# iF11M.net
KiCad netlist of a schematic drawn in Altium Designer
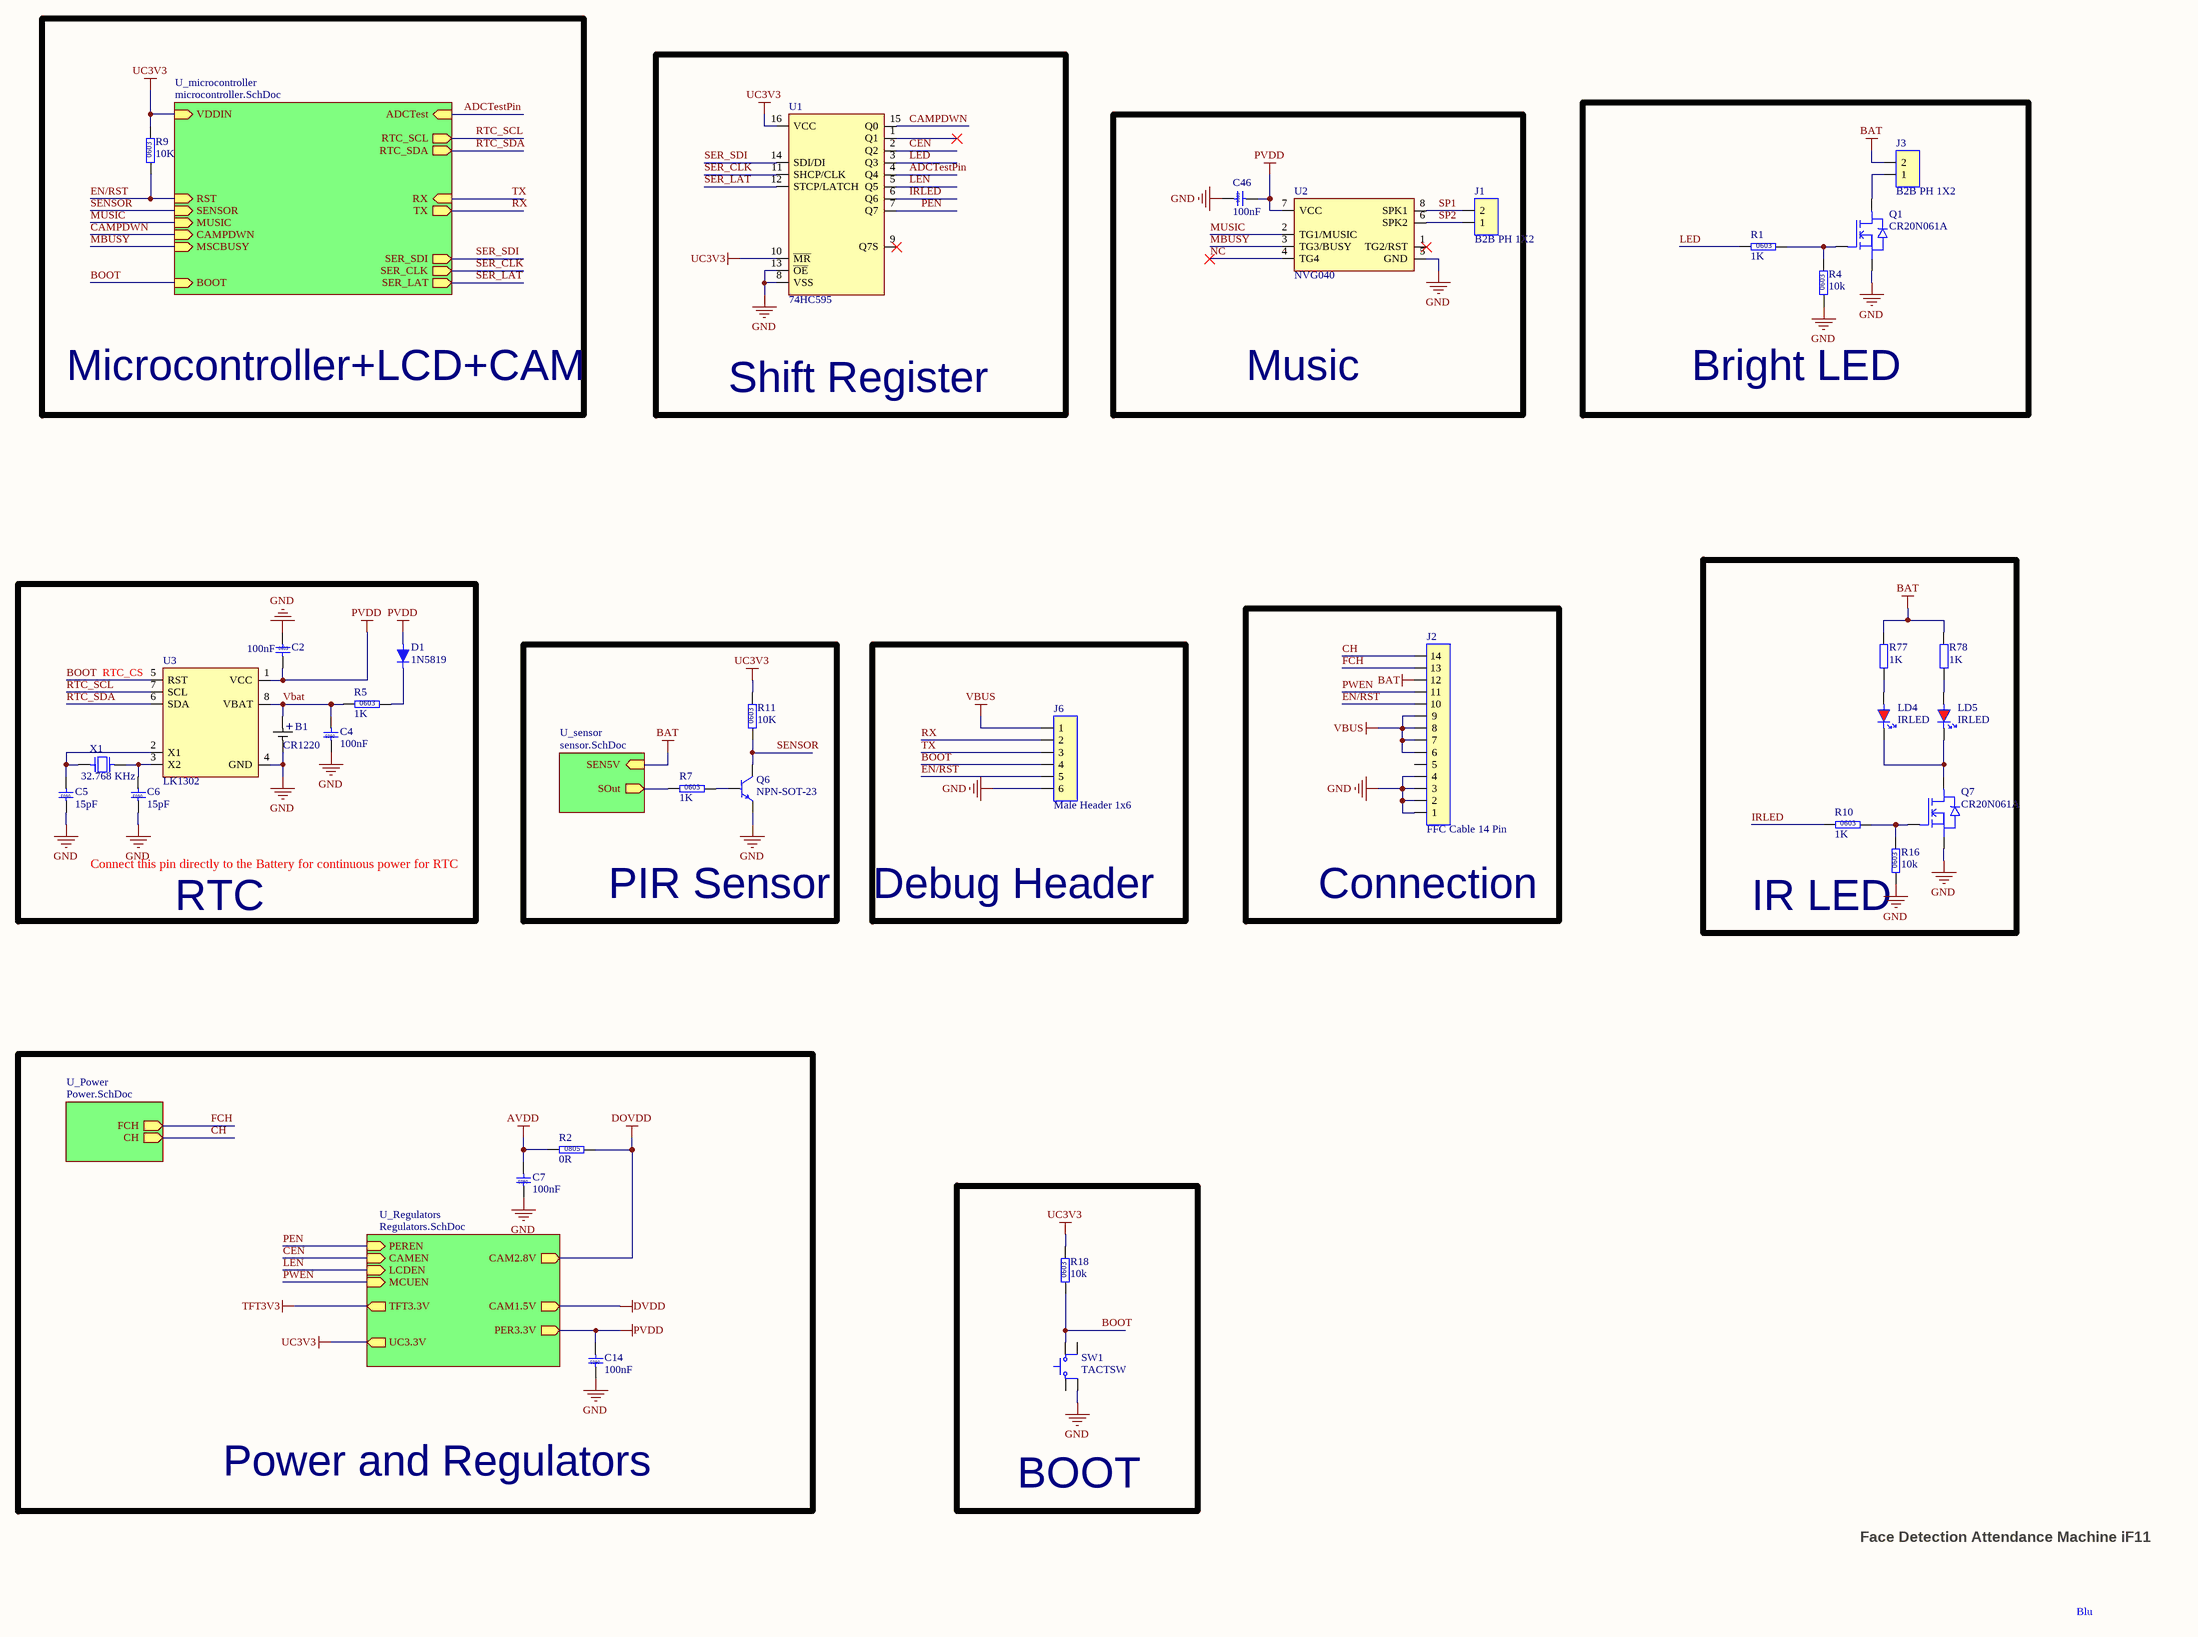
[diagram p0: iF11M.SchDoc]

(export (version "E")
  (design (tool "Eeschema 10.0.6"))
  (components
    (comp (ref "B1") (value "CR1220") (footprint "CR1220") (libsource (lib "Others") (part "CR1220")))
    (comp (ref "C2")
      (value "100nF")
      (footprint "C0603")
      (description "10% 50V")
      (fields (field (name "PART NO") "W-T-CA-X703N100K50VNT") (field (name "MANUFACTURER") "FENGHUA"))
      (libsource (lib "Rescap") (part "C 0603 100nF 50V"))
    )
    (comp (ref "C4")
      (value "100nF")
      (footprint "C0603")
      (description "10% 50V")
      (fields (field (name "PART NO") "W-T-CA-X703N100K50VNT") (field (name "MANUFACTURER") "FENGHUA"))
      (libsource (lib "Rescap") (part "C 0603 100nF 50V"))
    )
    (comp (ref "C5")
      (value "15pF")
      (footprint "C0603")
      (description "5% 25V")
      (fields (field (name "PART NO") "W-T-CA-CG03P010J25VNT"))
      (libsource (lib "Rescap") (part "C 0603 10pF 25V"))
    )
    (comp (ref "C6")
      (value "15pF")
      (footprint "C0603")
      (description "5% 25V")
      (fields (field (name "PART NO") "W-T-CA-CG03P010J25VNT"))
      (libsource (lib "Rescap") (part "C 0603 10pF 25V"))
    )
    (comp (ref "C7")
      (value "100nF")
      (footprint "C0603")
      (description "10% 50V")
      (fields (field (name "PART NO") "W-T-CA-X703N100K50VNT") (field (name "MANUFACTURER") "FENGHUA"))
      (libsource (lib "Rescap") (part "C 0603 100nF 50V"))
    )
    (comp (ref "C14")
      (value "100nF")
      (footprint "C0603")
      (description "10% 50V")
      (fields (field (name "PART NO") "W-T-CA-X703N100K50VNT") (field (name "MANUFACTURER") "FENGHUA"))
      (libsource (lib "Rescap") (part "C 0603 100nF 50V"))
    )
    (comp (ref "C46")
      (value "100nF")
      (footprint "C0603")
      (description "10% 50V")
      (fields (field (name "PART NO") "W-T-CA-X703N100K50VNT") (field (name "MANUFACTURER") "FENGHUA"))
      (libsource (lib "Rescap") (part "C 0603 100nF 50V"))
    )
    (comp (ref "D1") (value "1N5819") (footprint "SOD-323") (libsource (lib "Rectifier") (part "IN4148")))
    (comp (ref "J1")
      (value "B2B PH 1X2")
      (footprint "B2B-PH-2mm")
      (description "2 Pin B2B Connector")
      (libsource (lib "Connector") (part "B2B-PH-2MM"))
    )
    (comp (ref "J2")
      (value "FFC Cable 14 Pin")
      (footprint "FPC14P-1.2mm-THT")
      (libsource (lib "Connector") (part "FFC14P"))
    )
    (comp (ref "J3")
      (value "B2B PH 1X2")
      (footprint "B2B-PH-2mm")
      (description "2 Pin B2B Connector")
      (libsource (lib "Connector") (part "B2B-PH-2MM"))
    )
    (comp (ref "J6")
      (value "Male Header 1x6")
      (footprint "MHEADER-1x6")
      (description "6 Pin Male Header")
      (libsource (lib "Connector") (part "MHeader-1x6"))
    )
    (comp (ref "LD4")
      (value "IRLED")
      (footprint "LED 5mm RED Bent")
      (libsource (lib "Optoelectronics") (part "IRLED"))
    )
    (comp (ref "LD5")
      (value "IRLED")
      (footprint "LED 5mm RED Bent")
      (libsource (lib "Optoelectronics") (part "IRLED"))
    )
    (comp (ref "Q1")
      (value "CR20N061A")
      (footprint "NMOS-SOT23")
      (description "MOSFET-N-Channel")
      (libsource (lib "Transistor") (part "MOSFET-N-Channel"))
    )
    (comp (ref "Q6")
      (value "NPN-SOT-23")
      (footprint "SOT23")
      (libsource (lib "Transistor") (part "NPN-SOT-23"))
    )
    (comp (ref "Q7")
      (value "CR20N061A")
      (footprint "NMOS-SOT23")
      (description "MOSFET-N-Channel")
      (libsource (lib "Transistor") (part "MOSFET-N-Channel"))
    )
    (comp (ref "R1")
      (value "1K")
      (footprint "R0603-LD")
      (description "5%")
      (fields (field (name "PART NO") "W-T-RE-RS03K103JT") (field (name "MANUFACTURER") "热敏D541V11增加1颗用量"))
      (libsource (lib "Rescap") (part "R 0603 10k"))
    )
    (comp (ref "R2")
      (value "0R")
      (footprint "R0805-LD")
      (description "1%")
      (fields (field (name "PART NO") "W-T-RE-RS05K0R0JT"))
      (libsource (lib "Rescap") (part "R 0805 0R"))
    )
    (comp (ref "R4")
      (value "10k")
      (footprint "R0603-LD")
      (description "5%")
      (fields (field (name "PART NO") "W-T-RE-RS03K103JT") (field (name "MANUFACTURER") "热敏D541V11增加1颗用量"))
      (libsource (lib "Rescap") (part "R 0603 10k"))
    )
    (comp (ref "R5")
      (value "1K")
      (footprint "R0603-LD")
      (description "5%")
      (fields (field (name "PART NO") "W-T-RE-RS03K103JT") (field (name "MANUFACTURER") "热敏D541V11增加1颗用量"))
      (libsource (lib "Rescap") (part "R 0603 10k"))
    )
    (comp (ref "R7")
      (value "1K")
      (footprint "R0603-LD")
      (description "5%")
      (fields (field (name "PART NO") "W-T-RE-RS03K103JT") (field (name "MANUFACTURER") "热敏D541V11增加1颗用量"))
      (libsource (lib "Rescap") (part "R 0603 10k"))
    )
    (comp (ref "R9")
      (value "10K")
      (footprint "R0603-LD")
      (description "5%")
      (fields (field (name "PART NO") "W-T-RE-RS03K103JT") (field (name "MANUFACTURER") "热敏D541V11增加1颗用量"))
      (libsource (lib "Rescap") (part "R 0603 10K"))
    )
    (comp (ref "R10")
      (value "1K")
      (footprint "R0603-LD")
      (description "5%")
      (fields (field (name "PART NO") "W-T-RE-RS03K103JT") (field (name "MANUFACTURER") "热敏D541V11增加1颗用量"))
      (libsource (lib "Rescap") (part "R 0603 10k"))
    )
    (comp (ref "R11")
      (value "10K")
      (footprint "R0603-LD")
      (description "5%")
      (fields (field (name "PART NO") "W-T-RE-RS03K103JT") (field (name "MANUFACTURER") "热敏D541V11增加1颗用量"))
      (libsource (lib "Rescap") (part "R 0603 10K"))
    )
    (comp (ref "R16")
      (value "10k")
      (footprint "R0603-LD")
      (description "5%")
      (fields (field (name "PART NO") "W-T-RE-RS03K103JT") (field (name "MANUFACTURER") "热敏D541V11增加1颗用量"))
      (libsource (lib "Rescap") (part "R 0603 10k"))
    )
    (comp (ref "R18")
      (value "10k")
      (footprint "R0603-LD")
      (description "5%")
      (fields (field (name "PART NO") "W-T-RE-RS03K103JT") (field (name "MANUFACTURER") "热敏D541V11增加1颗用量"))
      (libsource (lib "Rescap") (part "R 0603 10k"))
    )
    (comp (ref "R77") (value "1K") (footprint "R0805") (libsource (lib "Resistor") (part "Resistor")))
    (comp (ref "R78") (value "1K") (footprint "R0805") (libsource (lib "Resistor") (part "Resistor")))
    (comp (ref "SW1")
      (value "TACTSW")
      (footprint "SMDtactswitch-5x5")
      (description "2 pin tactile switch round")
      (libsource (lib "Switch") (part "Tactile-smd_1"))
    )
    (comp (ref "U1")
      (value "74HC595")
      (footprint "SOIC16")
      (description "8bit Serial/Parallel Shift Register")
      (libsource (lib "mylib2") (part "74595"))
    )
    (comp (ref "U2") (value "NVG040") (footprint "SOP-8") (libsource (lib "mylib2") (part "NVG040")))
    (comp (ref "U3")
      (value "LK1302")
      (footprint "SOP-8")
      (description "Trickle-Charge Timekeeping Chip")
      (libsource (lib "mylib2") (part "LK1302"))
    )
    (comp (ref "X1")
      (value "32.768 KHz")
      (footprint "RTC Crystal")
      (description "RTC Crystal")
      (libsource (lib "Others") (part "Crystal_RTC"))
    )
  )
  (nets
    (net (code "1") (name "/ADCTestPin") (class "Default")
      (node (ref "U1") (pin "4") (pinfunction "Q4_4") (pintype "passive"))
    )
    (net (code "2") (name "/BOOT") (class "Default")
      (node (ref "J6") (pin "4") (pinfunction "4_4") (pintype "passive"))
      (node (ref "R18") (pin "1") (pinfunction "1_1") (pintype "passive"))
      (node (ref "SW1") (pin "4") (pinfunction "4_4") (pintype "passive"))
      (node (ref "U3") (pin "5") (pinfunction "RST_5") (pintype "passive"))
    )
    (net (code "3") (name "/CAMPDWN") (class "Default")
      (node (ref "U1") (pin "15") (pinfunction "Q0_15") (pintype "passive"))
    )
    (net (code "4") (name "/CEN") (class "Default")
      (node (ref "U1") (pin "2") (pinfunction "Q2_2") (pintype "passive"))
    )
    (net (code "5") (name "/CH") (class "Default")
      (node (ref "J2") (pin "14") (pinfunction "14_14") (pintype "passive"))
    )
    (net (code "6") (name "/EN{slash}RST") (class "Default")
      (node (ref "J2") (pin "10") (pinfunction "10_10") (pintype "passive"))
      (node (ref "J6") (pin "5") (pinfunction "5_5") (pintype "passive"))
      (node (ref "R9") (pin "1") (pinfunction "1_1") (pintype "passive"))
    )
    (net (code "7") (name "/FCH") (class "Default")
      (node (ref "J2") (pin "13") (pinfunction "13_13") (pintype "passive"))
    )
    (net (code "8") (name "/IRLED") (class "Default")
      (node (ref "R10") (pin "1") (pinfunction "1_1") (pintype "passive"))
      (node (ref "U1") (pin "6") (pinfunction "Q6_6") (pintype "passive"))
    )
    (net (code "9") (name "/LED") (class "Default")
      (node (ref "R1") (pin "1") (pinfunction "1_1") (pintype "passive"))
      (node (ref "U1") (pin "3") (pinfunction "Q3_3") (pintype "passive"))
    )
    (net (code "10") (name "/LEN") (class "Default")
      (node (ref "U1") (pin "5") (pinfunction "Q5_5") (pintype "passive"))
    )
    (net (code "11") (name "/MBUSY") (class "Default")
      (node (ref "U2") (pin "3") (pinfunction "TG3/BUSY_3") (pintype "passive"))
    )
    (net (code "12") (name "/MUSIC") (class "Default")
      (node (ref "U2") (pin "2") (pinfunction "TG1/MUSIC_2") (pintype "passive"))
    )
    (net (code "13") (name "/NC") (class "Default")
      (node (ref "U2") (pin "4") (pinfunction "TG4_4") (pintype "passive+no_connect"))
    )
    (net (code "14") (name "/PEN") (class "Default")
      (node (ref "U1") (pin "7") (pinfunction "Q7_7") (pintype "passive"))
    )
    (net (code "15") (name "/PWEN") (class "Default")
      (node (ref "J2") (pin "11") (pinfunction "11_11") (pintype "passive"))
    )
    (net (code "16") (name "/RTC_SCL") (class "Default")
      (node (ref "U3") (pin "7") (pinfunction "SCL_7") (pintype "passive"))
    )
    (net (code "17") (name "/RTC_SDA") (class "Default")
      (node (ref "U3") (pin "6") (pinfunction "SDA_6") (pintype "passive"))
    )
    (net (code "18") (name "/RX") (class "Default")
      (node (ref "J6") (pin "2") (pinfunction "2_2") (pintype "passive"))
    )
    (net (code "19") (name "/SENSOR") (class "Default")
      (node (ref "Q6") (pin "3") (pinfunction "C_3") (pintype "passive"))
      (node (ref "R11") (pin "1") (pinfunction "1_1") (pintype "passive"))
    )
    (net (code "20") (name "/SER_CLK") (class "Default")
      (node (ref "U1") (pin "11") (pinfunction "SHCP/CLK_11") (pintype "passive"))
    )
    (net (code "21") (name "/SER_LAT") (class "Default")
      (node (ref "U1") (pin "12") (pinfunction "STCP/LATCH_12") (pintype "passive"))
    )
    (net (code "22") (name "/SER_SDI") (class "Default")
      (node (ref "U1") (pin "14") (pinfunction "SDI/DI_14") (pintype "passive"))
    )
    (net (code "23") (name "/SOut") (class "Default")
      (node (ref "R7") (pin "1") (pinfunction "1_1") (pintype "passive"))
    )
    (net (code "24") (name "/SP1") (class "Default")
      (node (ref "J1") (pin "2") (pinfunction "2_2") (pintype "passive"))
      (node (ref "U2") (pin "8") (pinfunction "SPK1_8") (pintype "passive"))
    )
    (net (code "25") (name "/SP2") (class "Default")
      (node (ref "J1") (pin "1") (pinfunction "1_1") (pintype "passive"))
      (node (ref "U2") (pin "6") (pinfunction "SPK2_6") (pintype "passive"))
    )
    (net (code "26") (name "/TX") (class "Default")
      (node (ref "J6") (pin "3") (pinfunction "3_3") (pintype "passive"))
    )
    (net (code "27") (name "/Vbat") (class "Default")
      (node (ref "B1") (pin "2") (pinfunction "2_2") (pintype "passive"))
      (node (ref "C4") (pin "2") (pinfunction "2_2") (pintype "passive"))
      (node (ref "R5") (pin "1") (pinfunction "1_1") (pintype "passive"))
      (node (ref "U3") (pin "8") (pinfunction "VBAT_8") (pintype "passive"))
    )
    (net (code "28") (name "AVDD") (class "Default")
      (node (ref "C7") (pin "2") (pinfunction "2_2") (pintype "passive"))
      (node (ref "R2") (pin "1") (pinfunction "1_1") (pintype "passive"))
    )
    (net (code "29") (name "BAT") (class "Default")
      (node (ref "J2") (pin "12") (pinfunction "12_12") (pintype "passive"))
      (node (ref "J3") (pin "2") (pinfunction "2_2") (pintype "passive"))
      (node (ref "R77") (pin "2") (pinfunction "2_2") (pintype "passive"))
      (node (ref "R78") (pin "2") (pinfunction "2_2") (pintype "passive"))
    )
    (net (code "30") (name "DOVDD") (class "Default")
      (node (ref "R2") (pin "2") (pinfunction "2_2") (pintype "passive"))
    )
    (net (code "32") (name "GND") (class "Default")
      (node (ref "B1") (pin "1") (pinfunction "1_1") (pintype "passive"))
      (node (ref "C14") (pin "1") (pinfunction "1_1") (pintype "passive"))
      (node (ref "C2") (pin "1") (pinfunction "1_1") (pintype "passive"))
      (node (ref "C4") (pin "1") (pinfunction "1_1") (pintype "passive"))
      (node (ref "C46") (pin "1") (pinfunction "1_1") (pintype "passive"))
      (node (ref "C5") (pin "1") (pinfunction "1_1") (pintype "passive"))
      (node (ref "C6") (pin "1") (pinfunction "1_1") (pintype "passive"))
      (node (ref "C7") (pin "1") (pinfunction "1_1") (pintype "passive"))
      (node (ref "J2") (pin "1") (pinfunction "1_1") (pintype "passive"))
      (node (ref "J2") (pin "2") (pinfunction "2_2") (pintype "passive"))
      (node (ref "J2") (pin "3") (pinfunction "3_3") (pintype "passive"))
      (node (ref "J2") (pin "4") (pinfunction "4_4") (pintype "passive"))
      (node (ref "J6") (pin "6") (pinfunction "6_6") (pintype "passive"))
      (node (ref "Q1") (pin "3") (pinfunction "S_3") (pintype "passive"))
      (node (ref "Q6") (pin "2") (pinfunction "E_2") (pintype "passive"))
      (node (ref "Q7") (pin "3") (pinfunction "S_3") (pintype "passive"))
      (node (ref "R16") (pin "1") (pinfunction "1_1") (pintype "passive"))
      (node (ref "R4") (pin "1") (pinfunction "1_1") (pintype "passive"))
      (node (ref "SW1") (pin "2") (pinfunction "2_2") (pintype "passive"))
      (node (ref "U1") (pin "13") (pinfunction "~{OE}_13") (pintype "passive"))
      (node (ref "U1") (pin "8") (pinfunction "VSS_8") (pintype "passive"))
      (node (ref "U2") (pin "5") (pinfunction "GND_5") (pintype "passive"))
      (node (ref "U3") (pin "4") (pinfunction "GND_4") (pintype "passive"))
    )
    (net (code "33") (name "Net-(D1-K)") (class "Default")
      (node (ref "D1") (pin "2") (pinfunction "K_2") (pintype "passive"))
      (node (ref "R5") (pin "2") (pinfunction "2_2") (pintype "passive"))
    )
    (net (code "34") (name "Net-(LD4-A)") (class "Default")
      (node (ref "LD4") (pin "1") (pinfunction "A_1") (pintype "passive"))
      (node (ref "R77") (pin "1") (pinfunction "1_1") (pintype "passive"))
    )
    (net (code "35") (name "Net-(LD4-K)") (class "Default")
      (node (ref "LD4") (pin "2") (pinfunction "K_2") (pintype "passive"))
      (node (ref "LD5") (pin "2") (pinfunction "K_2") (pintype "passive"))
      (node (ref "Q7") (pin "2") (pinfunction "D_2") (pintype "passive"))
    )
    (net (code "36") (name "Net-(LD5-A)") (class "Default")
      (node (ref "LD5") (pin "1") (pinfunction "A_1") (pintype "passive"))
      (node (ref "R78") (pin "1") (pinfunction "1_1") (pintype "passive"))
    )
    (net (code "37") (name "Net-(Q1-D)") (class "Default")
      (node (ref "J3") (pin "1") (pinfunction "1_1") (pintype "passive"))
      (node (ref "Q1") (pin "2") (pinfunction "D_2") (pintype "passive"))
    )
    (net (code "38") (name "Net-(Q1-G)") (class "Default")
      (node (ref "Q1") (pin "1") (pinfunction "G_1") (pintype "passive"))
      (node (ref "R1") (pin "2") (pinfunction "2_2") (pintype "passive"))
      (node (ref "R4") (pin "2") (pinfunction "2_2") (pintype "passive"))
    )
    (net (code "39") (name "Net-(Q6-B)") (class "Default")
      (node (ref "Q6") (pin "1") (pinfunction "B_1") (pintype "passive"))
      (node (ref "R7") (pin "2") (pinfunction "2_2") (pintype "passive"))
    )
    (net (code "40") (name "Net-(Q7-G)") (class "Default")
      (node (ref "Q7") (pin "1") (pinfunction "G_1") (pintype "passive"))
      (node (ref "R10") (pin "2") (pinfunction "2_2") (pintype "passive"))
      (node (ref "R16") (pin "2") (pinfunction "2_2") (pintype "passive"))
    )
    (net (code "41") (name "Net-(U3-X1)") (class "Default")
      (node (ref "C5") (pin "2") (pinfunction "2_2") (pintype "passive"))
      (node (ref "U3") (pin "2") (pinfunction "X1_2") (pintype "passive"))
      (node (ref "X1") (pin "2") (pinfunction "2_2") (pintype "passive"))
    )
    (net (code "42") (name "Net-(U3-X2)") (class "Default")
      (node (ref "C6") (pin "2") (pinfunction "2_2") (pintype "passive"))
      (node (ref "U3") (pin "3") (pinfunction "X2_3") (pintype "passive"))
      (node (ref "X1") (pin "1") (pinfunction "1_1") (pintype "passive"))
    )
    (net (code "43") (name "PVDD") (class "Default")
      (node (ref "C14") (pin "2") (pinfunction "2_2") (pintype "passive"))
      (node (ref "C2") (pin "2") (pinfunction "2_2") (pintype "passive"))
      (node (ref "C46") (pin "2") (pinfunction "2_2") (pintype "passive"))
      (node (ref "D1") (pin "1") (pinfunction "A_1") (pintype "passive"))
      (node (ref "U2") (pin "7") (pinfunction "VCC_7") (pintype "passive"))
      (node (ref "U3") (pin "1") (pinfunction "VCC_1") (pintype "passive"))
    )
    (net (code "45") (name "UC3V3") (class "Default")
      (node (ref "R11") (pin "2") (pinfunction "2_2") (pintype "passive"))
      (node (ref "R18") (pin "2") (pinfunction "2_2") (pintype "passive"))
      (node (ref "R9") (pin "2") (pinfunction "2_2") (pintype "passive"))
      (node (ref "U1") (pin "10") (pinfunction "~{MR}_10") (pintype "passive"))
      (node (ref "U1") (pin "16") (pinfunction "VCC_16") (pintype "passive"))
    )
    (net (code "46") (name "VBUS") (class "Default")
      (node (ref "J2") (pin "6") (pinfunction "6_6") (pintype "passive"))
      (node (ref "J2") (pin "7") (pinfunction "7_7") (pintype "passive"))
      (node (ref "J2") (pin "8") (pinfunction "8_8") (pintype "passive"))
      (node (ref "J2") (pin "9") (pinfunction "9_9") (pintype "passive"))
      (node (ref "J6") (pin "1") (pinfunction "1_1") (pintype "passive"))
    )
    (net (code "47") (name "unconnected-(J2-Pad5)") (class "Default")
      (node (ref "J2") (pin "5") (pinfunction "5_5") (pintype "passive"))
    )
    (net (code "48") (name "unconnected-(SW1-Pad1)") (class "Default")
      (node (ref "SW1") (pin "1") (pinfunction "1_1") (pintype "passive"))
    )
    (net (code "49") (name "unconnected-(SW1-Pad3)") (class "Default")
      (node (ref "SW1") (pin "3") (pinfunction "3_3") (pintype "passive"))
    )
    (net (code "50") (name "unconnected-(U1-Q1-Pad1)") (class "Default")
      (node (ref "U1") (pin "1") (pinfunction "Q1_1") (pintype "passive+no_connect"))
    )
    (net (code "51") (name "unconnected-(U1-Q7S-Pad9)") (class "Default")
      (node (ref "U1") (pin "9") (pinfunction "Q7S_9") (pintype "passive+no_connect"))
    )
    (net (code "52") (name "unconnected-(U2-TG2{slash}RST-Pad1)") (class "Default")
      (node (ref "U2") (pin "1") (pinfunction "TG2/RST_1") (pintype "passive+no_connect"))
    )
  )
)
